# schematic.net
KiCad netlist of a schematic drawn in EAGLE
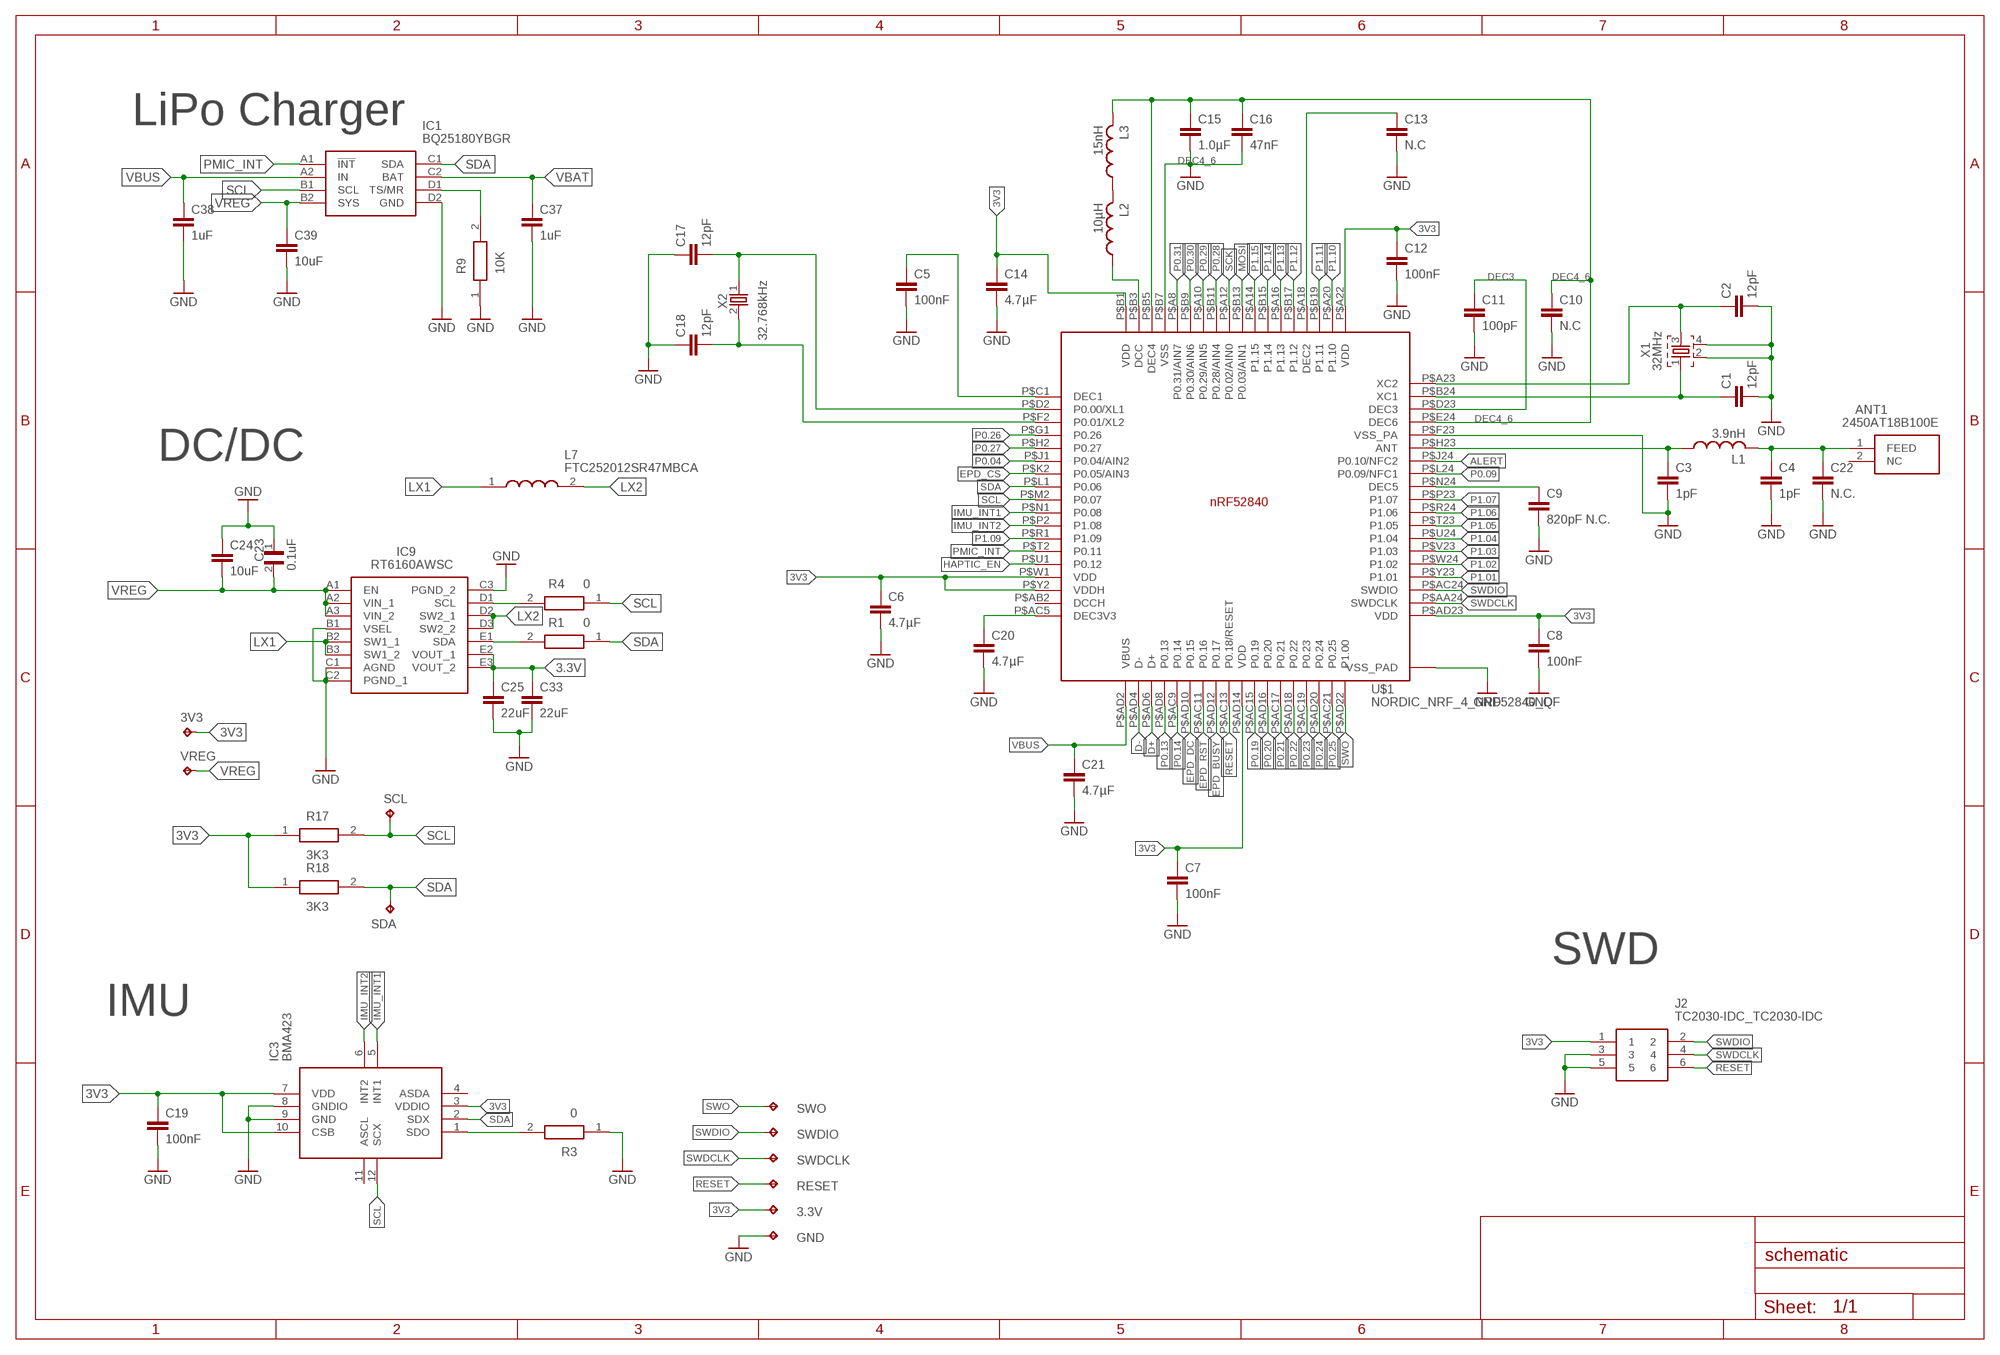
[diagram p0: schematic, sheet 1, part 1 of 2]
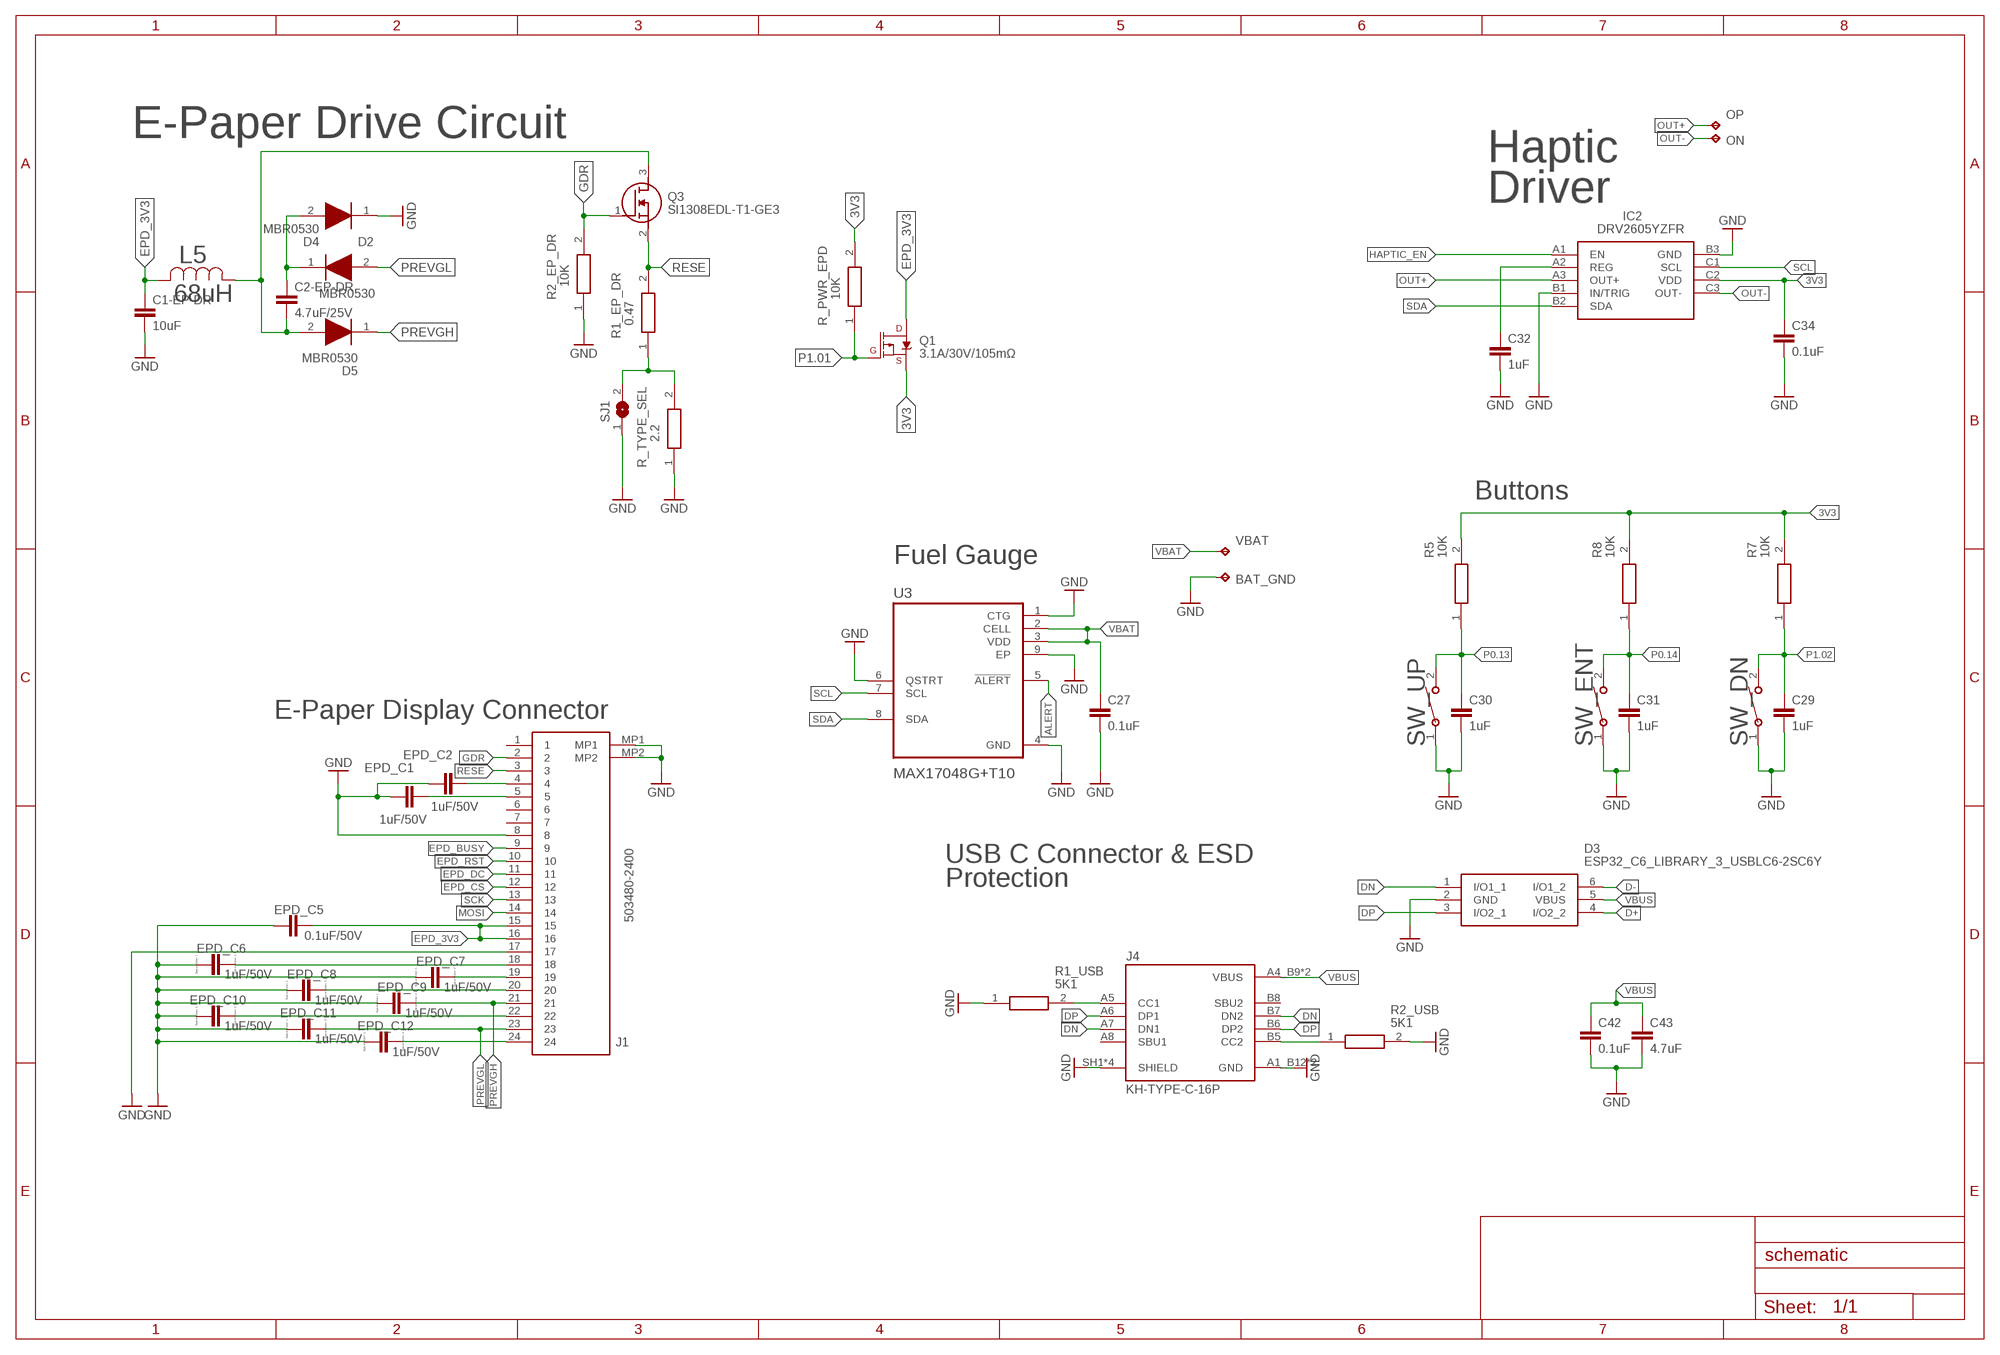
[diagram p1: schematic, sheet 1, part 2 of 2]

(export (version "E")
  (design (tool "Eeschema 10.0.6"))
  (components
    (comp (ref "3.3V")
      (value "HECTOR_WATCH_1_TPTP20R")
      (footprint "eagle-import:HECTOR_WATCH_1_TP20R")
      (libsource (lib "eagle-import") (part "HECTOR_WATCH_1_TPTP20R"))
    )
    (comp (ref "3V3")
      (value "HECTOR_WATCH_1_TPTP20R")
      (footprint "eagle-import:HECTOR_WATCH_1_TP20R")
      (libsource (lib "eagle-import") (part "HECTOR_WATCH_1_TPTP20R"))
    )
    (comp (ref "ANT1")
      (value "2450AT18B100E")
      (footprint "eagle-import:2450AT18B100E_ANTC3216X140N")
      (fields (field (name "MOUSER_PART_NUMBER") "609-2450AT18B100E"))
      (libsource (lib "eagle-import") (part "2450AT18B100E_2450AT18B100E"))
    )
    (comp (ref "BAT_GND")
      (value "HECTOR_WATCH_1_TPTP20R")
      (footprint "eagle-import:HECTOR_WATCH_1_TP20R")
      (libsource (lib "eagle-import") (part "HECTOR_WATCH_1_TPTP20R"))
    )
    (comp (ref "C1")
      (value "12pF")
      (footprint "eagle-import:NORDIC_NRF_3_RESC0201_N")
      (libsource (lib "eagle-import") (part "NORDIC_NRF_3_CAPACITOR_0201_N"))
    )
    (comp (ref "C1-EP-DR")
      (value "10uF")
      (footprint "eagle-import:NORDIC_NRF_3_RESC0402_N")
      (libsource (lib "eagle-import") (part "NORDIC_NRF_3_CAPACITOR_0402_N"))
    )
    (comp (ref "C2")
      (value "12pF")
      (footprint "eagle-import:NORDIC_NRF_3_RESC0201_N")
      (libsource (lib "eagle-import") (part "NORDIC_NRF_3_CAPACITOR_0201_N"))
    )
    (comp (ref "C2-EP-DR")
      (value "4.7uF/25V")
      (footprint "eagle-import:NORDIC_NRF_3_RESC0402_N")
      (libsource (lib "eagle-import") (part "NORDIC_NRF_3_CAPACITOR_0402_N"))
    )
    (comp (ref "C3")
      (value "1pF")
      (footprint "eagle-import:NORDIC_NRF_3_RESC0201_N")
      (libsource (lib "eagle-import") (part "NORDIC_NRF_3_CAPACITOR_0201_N"))
    )
    (comp (ref "C4")
      (value "1pF")
      (footprint "eagle-import:NORDIC_NRF_3_RESC0201_N")
      (libsource (lib "eagle-import") (part "NORDIC_NRF_3_CAPACITOR_0201_N"))
    )
    (comp (ref "C5")
      (value "100nF")
      (footprint "eagle-import:NORDIC_NRF_3_RESC0201_N")
      (libsource (lib "eagle-import") (part "NORDIC_NRF_3_CAPACITOR_0201_N"))
    )
    (comp (ref "C6")
      (value "4.7µF")
      (footprint "eagle-import:NORDIC_NRF_3_RESC0402_N")
      (libsource (lib "eagle-import") (part "NORDIC_NRF_3_CAPACITOR_0402_N"))
    )
    (comp (ref "C7")
      (value "100nF")
      (footprint "eagle-import:NORDIC_NRF_3_RESC0201_N")
      (libsource (lib "eagle-import") (part "NORDIC_NRF_3_CAPACITOR_0201_N"))
    )
    (comp (ref "C8")
      (value "100nF")
      (footprint "eagle-import:NORDIC_NRF_3_RESC0201_N")
      (libsource (lib "eagle-import") (part "NORDIC_NRF_3_CAPACITOR_0201_N"))
    )
    (comp (ref "C9")
      (value "820pF N.C.")
      (footprint "eagle-import:NORDIC_NRF_3_RESC0201_N")
      (libsource (lib "eagle-import") (part "NORDIC_NRF_3_CAPACITOR_0201_N"))
    )
    (comp (ref "C10")
      (value "N.C")
      (footprint "eagle-import:NORDIC_NRF_3_RESC0201_N")
      (libsource (lib "eagle-import") (part "NORDIC_NRF_3_CAPACITOR_0201_N"))
    )
    (comp (ref "C11")
      (value "100pF")
      (footprint "eagle-import:NORDIC_NRF_3_RESC0201_N")
      (libsource (lib "eagle-import") (part "NORDIC_NRF_3_CAPACITOR_0201_N"))
    )
    (comp (ref "C12")
      (value "100nF")
      (footprint "eagle-import:NORDIC_NRF_3_RESC0201_N")
      (libsource (lib "eagle-import") (part "NORDIC_NRF_3_CAPACITOR_0201_N"))
    )
    (comp (ref "C13")
      (value "N.C")
      (footprint "eagle-import:NORDIC_NRF_3_RESC0201_N")
      (libsource (lib "eagle-import") (part "NORDIC_NRF_3_CAPACITOR_0201_N"))
    )
    (comp (ref "C14")
      (value "4.7µF")
      (footprint "eagle-import:NORDIC_NRF_3_RESC0402_M")
      (libsource (lib "eagle-import") (part "NORDIC_NRF_3_CAPACITOR_0402_M"))
    )
    (comp (ref "C15")
      (value "1.0µF")
      (footprint "eagle-import:NORDIC_NRF_3_RESC0402_M")
      (libsource (lib "eagle-import") (part "NORDIC_NRF_3_CAPACITOR_0402_M"))
    )
    (comp (ref "C16")
      (value "47nF")
      (footprint "eagle-import:NORDIC_NRF_3_RESC0201_N")
      (libsource (lib "eagle-import") (part "NORDIC_NRF_3_CAPACITOR_0201_N"))
    )
    (comp (ref "C17")
      (value "12pF")
      (footprint "eagle-import:NORDIC_NRF_3_RESC0201_N")
      (libsource (lib "eagle-import") (part "NORDIC_NRF_3_CAPACITOR_0201_N"))
    )
    (comp (ref "C18")
      (value "12pF")
      (footprint "eagle-import:NORDIC_NRF_3_RESC0201_N")
      (libsource (lib "eagle-import") (part "NORDIC_NRF_3_CAPACITOR_0201_N"))
    )
    (comp (ref "C19")
      (value "100nF")
      (footprint "eagle-import:NORDIC_NRF_3_RESC0201_N")
      (libsource (lib "eagle-import") (part "NORDIC_NRF_3_CAPACITOR_0201_N"))
    )
    (comp (ref "C20")
      (value "4.7µF")
      (footprint "eagle-import:NORDIC_NRF_3_RESC0402_N")
      (libsource (lib "eagle-import") (part "NORDIC_NRF_3_CAPACITOR_0402_N"))
    )
    (comp (ref "C21")
      (value "4.7µF")
      (footprint "eagle-import:NORDIC_NRF_3_RESC0402_N")
      (libsource (lib "eagle-import") (part "NORDIC_NRF_3_CAPACITOR_0402_N"))
    )
    (comp (ref "C22")
      (value "N.C.")
      (footprint "eagle-import:NORDIC_NRF_3_RESC0201_N")
      (libsource (lib "eagle-import") (part "NORDIC_NRF_3_CAPACITOR_0201_N"))
    )
    (comp (ref "C23")
      (value "0.1uF")
      (footprint "eagle-import:GRM011R60J152KE01L_1_0201")
      (fields (field (name "MF") "Murata") (field (name "MP") "GRM011R60J152KE01L"))
      (libsource (lib "eagle-import") (part "GRM011R60J152KE01L_2_GRM011R60J152KE01L"))
    )
    (comp (ref "C24")
      (value "10uF")
      (footprint "eagle-import:NORDIC_NRF_3_RESC0402_N")
      (libsource (lib "eagle-import") (part "NORDIC_NRF_3_CAPACITOR_0402_N"))
    )
    (comp (ref "C25")
      (value "22uF")
      (footprint "eagle-import:NORDIC_NRF_3_RESC0402_N")
      (libsource (lib "eagle-import") (part "NORDIC_NRF_3_CAPACITOR_0402_N"))
    )
    (comp (ref "C27")
      (value "0.1uF")
      (footprint "eagle-import:NORDIC_NRF_3_RESC0201_N")
      (libsource (lib "eagle-import") (part "NORDIC_NRF_3_CAPACITOR_0201_N"))
    )
    (comp (ref "C29")
      (value "1uF")
      (footprint "eagle-import:NORDIC_NRF_3_RESC0402_N")
      (libsource (lib "eagle-import") (part "NORDIC_NRF_3_CAPACITOR_0402_N"))
    )
    (comp (ref "C30")
      (value "1uF")
      (footprint "eagle-import:NORDIC_NRF_3_RESC0402_N")
      (libsource (lib "eagle-import") (part "NORDIC_NRF_3_CAPACITOR_0402_N"))
    )
    (comp (ref "C31")
      (value "1uF")
      (footprint "eagle-import:NORDIC_NRF_3_RESC0402_N")
      (libsource (lib "eagle-import") (part "NORDIC_NRF_3_CAPACITOR_0402_N"))
    )
    (comp (ref "C32")
      (value "1uF")
      (footprint "eagle-import:NORDIC_NRF_3_RESC0402_N")
      (libsource (lib "eagle-import") (part "NORDIC_NRF_3_CAPACITOR_0402_N"))
    )
    (comp (ref "C33")
      (value "22uF")
      (footprint "eagle-import:NORDIC_NRF_3_RESC0402_N")
      (libsource (lib "eagle-import") (part "NORDIC_NRF_3_CAPACITOR_0402_N"))
    )
    (comp (ref "C34")
      (value "0.1uF")
      (footprint "eagle-import:NORDIC_NRF_3_RESC0201_N")
      (libsource (lib "eagle-import") (part "NORDIC_NRF_3_CAPACITOR_0201_N"))
    )
    (comp (ref "C37")
      (value "1uF")
      (footprint "eagle-import:NORDIC_NRF_3_RESC0402_N")
      (libsource (lib "eagle-import") (part "NORDIC_NRF_3_CAPACITOR_0402_N"))
    )
    (comp (ref "C38")
      (value "1uF")
      (footprint "eagle-import:NORDIC_NRF_3_RESC0402_N")
      (libsource (lib "eagle-import") (part "NORDIC_NRF_3_CAPACITOR_0402_N"))
    )
    (comp (ref "C39")
      (value "10uF")
      (footprint "eagle-import:NORDIC_NRF_3_RESC0402_N")
      (libsource (lib "eagle-import") (part "NORDIC_NRF_3_CAPACITOR_0402_N"))
    )
    (comp (ref "C42")
      (value "0.1uF")
      (footprint "eagle-import:NORDIC_NRF_3_RESC0201_N")
      (libsource (lib "eagle-import") (part "NORDIC_NRF_3_CAPACITOR_0201_N"))
    )
    (comp (ref "C43")
      (value "4.7uF")
      (footprint "eagle-import:NORDIC_NRF_3_RESC0402_N")
      (libsource (lib "eagle-import") (part "NORDIC_NRF_3_CAPACITOR_0402_N"))
    )
    (comp (ref "D2")
      (value "MBR0530")
      (footprint "eagle-import:ESP32_C6_LIBRARY_5_SOD3716X135N")
      (fields (field (name "MF") "ON Semiconductor"))
      (libsource (lib "eagle-import") (part "ESP32_C6_LIBRARY_5_MBR0530"))
    )
    (comp (ref "D3")
      (value "ESP32_C6_LIBRARY_3_USBLC6-2SC6Y")
      (footprint "eagle-import:ESP32_C6_LIBRARY_3_SOT95P280X145-6N")
      (fields (field (name "MF") "STMicroelectronics") (field (name "MP") "USBLC6-2SC6Y"))
      (libsource (lib "eagle-import") (part "ESP32_C6_LIBRARY_3_USBLC6-2SC6Y"))
    )
    (comp (ref "D4")
      (value "MBR0530")
      (footprint "eagle-import:ESP32_C6_LIBRARY_5_SOD3716X135N")
      (fields (field (name "MF") "ON Semiconductor"))
      (libsource (lib "eagle-import") (part "ESP32_C6_LIBRARY_5_MBR0530"))
    )
    (comp (ref "D5")
      (value "MBR0530")
      (footprint "eagle-import:ESP32_C6_LIBRARY_5_SOD3716X135N")
      (fields (field (name "MF") "ON Semiconductor"))
      (libsource (lib "eagle-import") (part "ESP32_C6_LIBRARY_5_MBR0530"))
    )
    (comp (ref "EPD_C1")
      (value "1uF/50V")
      (footprint "eagle-import:NORDIC_NRF_3_RESC0402_N")
      (libsource (lib "eagle-import") (part "NORDIC_NRF_3_CAPACITOR_0402_N"))
    )
    (comp (ref "EPD_C2")
      (value "1uF/50V")
      (footprint "eagle-import:NORDIC_NRF_3_RESC0402_N")
      (libsource (lib "eagle-import") (part "NORDIC_NRF_3_CAPACITOR_0402_N"))
    )
    (comp (ref "EPD_C5")
      (value "0.1uF/50V")
      (footprint "eagle-import:NORDIC_NRF_3_RESC0201_N")
      (libsource (lib "eagle-import") (part "NORDIC_NRF_3_CAPACITOR_0201_N"))
    )
    (comp (ref "EPD_C6")
      (value "1uF/50V")
      (footprint "eagle-import:ESP32_C6_LIBRARY_1_ESP32_WROVER_EAGLE-LTSPICE_C0402")
      (libsource (lib "eagle-import") (part "ESP32_C6_LIBRARY_1_ESP32_WROVER_EAGLE-LTSPICE_CC0402"))
    )
    (comp (ref "EPD_C7")
      (value "1uF/50V")
      (footprint "eagle-import:ESP32_C6_LIBRARY_1_ESP32_WROVER_EAGLE-LTSPICE_C0402")
      (libsource (lib "eagle-import") (part "ESP32_C6_LIBRARY_1_ESP32_WROVER_EAGLE-LTSPICE_CC0402"))
    )
    (comp (ref "EPD_C8")
      (value "1uF/50V")
      (footprint "eagle-import:ESP32_C6_LIBRARY_1_ESP32_WROVER_EAGLE-LTSPICE_C0402")
      (libsource (lib "eagle-import") (part "ESP32_C6_LIBRARY_1_ESP32_WROVER_EAGLE-LTSPICE_CC0402"))
    )
    (comp (ref "EPD_C9")
      (value "1uF/50V")
      (footprint "eagle-import:ESP32_C6_LIBRARY_1_ESP32_WROVER_EAGLE-LTSPICE_C0402")
      (libsource (lib "eagle-import") (part "ESP32_C6_LIBRARY_1_ESP32_WROVER_EAGLE-LTSPICE_CC0402"))
    )
    (comp (ref "EPD_C10")
      (value "1uF/50V")
      (footprint "eagle-import:ESP32_C6_LIBRARY_1_ESP32_WROVER_EAGLE-LTSPICE_C0402")
      (libsource (lib "eagle-import") (part "ESP32_C6_LIBRARY_1_ESP32_WROVER_EAGLE-LTSPICE_CC0402"))
    )
    (comp (ref "EPD_C11")
      (value "1uF/50V")
      (footprint "eagle-import:ESP32_C6_LIBRARY_1_ESP32_WROVER_EAGLE-LTSPICE_C0402")
      (libsource (lib "eagle-import") (part "ESP32_C6_LIBRARY_1_ESP32_WROVER_EAGLE-LTSPICE_CC0402"))
    )
    (comp (ref "EPD_C12")
      (value "1uF/50V")
      (footprint "eagle-import:ESP32_C6_LIBRARY_1_ESP32_WROVER_EAGLE-LTSPICE_C0402")
      (libsource (lib "eagle-import") (part "ESP32_C6_LIBRARY_1_ESP32_WROVER_EAGLE-LTSPICE_CC0402"))
    )
    (comp (ref "GND")
      (value "HECTOR_WATCH_1_TPTP20R")
      (footprint "eagle-import:HECTOR_WATCH_1_TP20R")
      (libsource (lib "eagle-import") (part "HECTOR_WATCH_1_TPTP20R"))
    )
    (comp (ref "IC1")
      (value "BQ25180YBGR")
      (footprint "eagle-import:BQ25180YBGR_BGA8C40P2X4_100X155X50")
      (fields (field (name "MOUSER_PART_NUMBER") "595-BQ25180YBGR"))
      (libsource (lib "eagle-import") (part "BQ25180YBGR_BQ25180YBGR"))
    )
    (comp (ref "IC2")
      (value "DRV2605YZFR")
      (footprint "eagle-import:DRV2605YZFR_BGA9C50P3X3_144X144X62")
      (libsource (lib "eagle-import") (part "DRV2605YZFR_DRV2605YZFR"))
    )
    (comp (ref "IC3")
      (value "BMA423")
      (footprint "eagle-import:BMA423_BMA423")
      (fields (field (name "MOUSER_PART_NUMBER") "262-BMA423"))
      (libsource (lib "eagle-import") (part "BMA423_BMA423"))
    )
    (comp (ref "IC9")
      (value "RT6160AWSC")
      (footprint "eagle-import:RT6160AWSC_BGA15C40P3X5_140X230X60")
      (fields (field (name "MOUSER_PART_NUMBER") "835-RT6160AWSC"))
      (libsource (lib "eagle-import") (part "RT6160AWSC_RT6160AWSC"))
    )
    (comp (ref "J1")
      (value "503480-2400")
      (footprint "eagle-import:503480-2400_5034802400")
      (fields (field (name "MOUSER_PART_NUMBER") "538-503480-2400"))
      (libsource (lib "eagle-import") (part "503480-2400_503480-2400"))
    )
    (comp (ref "J2")
      (value "TC2030-IDC_TC2030-IDC")
      (footprint "eagle-import:TC2030-IDC_TC2030IDC")
      (fields (field (name "MANUFACTURER_PART_NUMBER") "TC2030-IDC"))
      (libsource (lib "eagle-import") (part "TC2030-IDC_TC2030-IDC"))
    )
    (comp (ref "J4")
      (value "KH-TYPE-C-16P")
      (footprint "eagle-import:KH-TYPE-C-16P_KINGHELM_KH-TYPE-C-16P")
      (fields (field (name "MF") "kinghelm"))
      (libsource (lib "eagle-import") (part "KH-TYPE-C-16P_KH-TYPE-C-16P"))
    )
    (comp (ref "L1")
      (value "3.9nH")
      (footprint "eagle-import:NORDIC_NRF_2_RESC0402_N")
      (libsource (lib "eagle-import") (part "NORDIC_NRF_2_INDUCTOR_0402_N"))
    )
    (comp (ref "L2")
      (value "10µH")
      (footprint "eagle-import:NORDIC_NRF_2_RESC0603_N")
      (libsource (lib "eagle-import") (part "NORDIC_NRF_2_INDUCTOR_0603_N"))
    )
    (comp (ref "L3")
      (value "15nH")
      (footprint "eagle-import:NORDIC_NRF_2_RESC0402_N")
      (libsource (lib "eagle-import") (part "NORDIC_NRF_2_INDUCTOR_0402_N"))
    )
    (comp (ref "L5")
      (value "68uH")
      (footprint "eagle-import:ESP32_C6_LIBRARY_2_IND_4828-WE-TPC_WRE")
      (fields
        (field (name "MANUFACTURER_PART_NUMBER") "744043680")
        (field (name "COPYRIGHT") "Copyright (C) 2024 Ultra Librarian. All rights reserved.")
      )
      (libsource (lib "eagle-import") (part "ESP32_C6_LIBRARY_2_744043680IND_4828-WE-TPC_WRE"))
    )
    (comp (ref "L7")
      (value "FTC252012SR47MBCA")
      (footprint "eagle-import:MLP2016SR47MT0S1_INDC2016X100N")
      (libsource (lib "eagle-import") (part "MLP2016SR47MT0S1_FTC252012SR47MBCA"))
    )
    (comp (ref "ON")
      (value "HECTOR_WATCH_1_TPTP20R")
      (footprint "eagle-import:HECTOR_WATCH_1_TP20R")
      (libsource (lib "eagle-import") (part "HECTOR_WATCH_1_TPTP20R"))
    )
    (comp (ref "OP")
      (value "HECTOR_WATCH_1_TPTP20R")
      (footprint "eagle-import:HECTOR_WATCH_1_TP20R")
      (libsource (lib "eagle-import") (part "HECTOR_WATCH_1_TPTP20R"))
    )
    (comp (ref "Q1")
      (value "3.1A/30V/105mΩ")
      (footprint "eagle-import:ESP32_C6_LIBRARY_4_ESP32_C6_LIBRARY_4_ESP32_C6_LIBRARY_4_ESP32_C6_LIBRARY_4_ESP32_WROVER_SPARKFUN-DISCRETESEMI_SOT23-3")
      (libsource (lib "eagle-import") (part "ESP32_C6_LIBRARY_4_ESP32_WROVER_SPARKFUN-DISCRETESEMI_MOSFET_PCH-DMG2307L"))
    )
    (comp (ref "Q3")
      (value "SI1308EDL-T1-GE3")
      (footprint "eagle-import:ESP32_C6_LIBRARY_6_SOT65P210X110-3N")
      (fields (field (name "MF") "Vishay Siliconix"))
      (libsource (lib "eagle-import") (part "ESP32_C6_LIBRARY_6_SI1308EDL-T1-GE3"))
    )
    (comp (ref "R1")
      (value "0")
      (footprint "eagle-import:ERA-1AEB3401C_0201")
      (libsource (lib "eagle-import") (part "ERA-1AEB3401C_CPF0201D7K68C1"))
    )
    (comp (ref "R1_EP_DR")
      (value "0.47")
      (footprint "eagle-import:CPF0201D7K68C1_0201")
      (libsource (lib "eagle-import") (part "CPF0201D7K68C1_CPF0201D7K68C1"))
    )
    (comp (ref "R1_USB")
      (value "5K1")
      (footprint "eagle-import:ERA-1AEB3401C_0201")
      (libsource (lib "eagle-import") (part "ERA-1AEB3401C_CPF0201D7K68C1"))
    )
    (comp (ref "R2_EP_DR")
      (value "10K")
      (footprint "eagle-import:CPF0201D7K68C1_0201")
      (libsource (lib "eagle-import") (part "CPF0201D7K68C1_CPF0201D7K68C1"))
    )
    (comp (ref "R2_USB")
      (value "5K1")
      (footprint "eagle-import:ERA-1AEB3401C_0201")
      (libsource (lib "eagle-import") (part "ERA-1AEB3401C_CPF0201D7K68C1"))
    )
    (comp (ref "R3")
      (value "0")
      (footprint "eagle-import:ERA-1AEB3401C_0201")
      (libsource (lib "eagle-import") (part "ERA-1AEB3401C_CPF0201D7K68C1"))
    )
    (comp (ref "R4")
      (value "0")
      (footprint "eagle-import:ERA-1AEB3401C_0201")
      (libsource (lib "eagle-import") (part "ERA-1AEB3401C_CPF0201D7K68C1"))
    )
    (comp (ref "R5")
      (value "10K")
      (footprint "eagle-import:CPF0201D7K68C1_0201")
      (libsource (lib "eagle-import") (part "CPF0201D7K68C1_CPF0201D7K68C1"))
    )
    (comp (ref "R7")
      (value "10K")
      (footprint "eagle-import:ERA-1AEB3401C_0201")
      (libsource (lib "eagle-import") (part "ERA-1AEB3401C_CPF0201D7K68C1"))
    )
    (comp (ref "R8")
      (value "10K")
      (footprint "eagle-import:CPF0201D7K68C1_0201")
      (libsource (lib "eagle-import") (part "CPF0201D7K68C1_CPF0201D7K68C1"))
    )
    (comp (ref "R9")
      (value "10K")
      (footprint "eagle-import:CPF0201D7K68C1_0201")
      (libsource (lib "eagle-import") (part "CPF0201D7K68C1_CPF0201D7K68C1"))
    )
    (comp (ref "R17")
      (value "3K3")
      (footprint "eagle-import:CPF0201D7K68C1_0201")
      (libsource (lib "eagle-import") (part "CPF0201D7K68C1_CPF0201D7K68C1"))
    )
    (comp (ref "R18")
      (value "3K3")
      (footprint "eagle-import:CPF0201D7K68C1_0201")
      (libsource (lib "eagle-import") (part "CPF0201D7K68C1_CPF0201D7K68C1"))
    )
    (comp (ref "RESET")
      (value "HECTOR_WATCH_1_TPTP20R")
      (footprint "eagle-import:HECTOR_WATCH_1_TP20R")
      (libsource (lib "eagle-import") (part "HECTOR_WATCH_1_TPTP20R"))
    )
    (comp (ref "R_PWR_EPD")
      (value "10K")
      (footprint "eagle-import:ERA-1AEB3401C_0201")
      (libsource (lib "eagle-import") (part "ERA-1AEB3401C_CPF0201D7K68C1"))
    )
    (comp (ref "R_TYPE_SEL")
      (value "2.2")
      (footprint "eagle-import:ERA-1AEB3401C_0201")
      (libsource (lib "eagle-import") (part "ERA-1AEB3401C_CPF0201D7K68C1"))
    )
    (comp (ref "SCL")
      (value "HECTOR_WATCH_1_TPTP20R")
      (footprint "eagle-import:HECTOR_WATCH_1_TP20R")
      (libsource (lib "eagle-import") (part "HECTOR_WATCH_1_TPTP20R"))
    )
    (comp (ref "SDA")
      (value "HECTOR_WATCH_1_TPTP20R")
      (footprint "eagle-import:HECTOR_WATCH_1_TP20R")
      (libsource (lib "eagle-import") (part "HECTOR_WATCH_1_TPTP20R"))
    )
    (comp (ref "SJ1")
      (value "ESP32_C6_LIBRARY_7_JUMPER_SJ")
      (footprint "eagle-import:ESP32_C6_LIBRARY_7_JUMPER_SJ")
      (libsource (lib "eagle-import") (part "ESP32_C6_LIBRARY_7_JUMPER_SJ"))
    )
    (comp (ref "SWDCLK")
      (value "HECTOR_WATCH_1_TPTP20R")
      (footprint "eagle-import:HECTOR_WATCH_1_TP20R")
      (libsource (lib "eagle-import") (part "HECTOR_WATCH_1_TPTP20R"))
    )
    (comp (ref "SWDIO")
      (value "HECTOR_WATCH_1_TPTP20R")
      (footprint "eagle-import:HECTOR_WATCH_1_TP20R")
      (libsource (lib "eagle-import") (part "HECTOR_WATCH_1_TPTP20R"))
    )
    (comp (ref "SWO")
      (value "HECTOR_WATCH_1_TPTP20R")
      (footprint "eagle-import:HECTOR_WATCH_1_TP20R")
      (libsource (lib "eagle-import") (part "HECTOR_WATCH_1_TPTP20R"))
    )
    (comp (ref "SW_DN")
      (value "2025-10-22_07-23-44_LIBRARY_EVP-AKE31ASW_EVP-AKE31A_PAN")
      (footprint "eagle-import:2025-10-22_07-23-44_LIBRARY_SW_EVP-AKE31A_PAN")
      (fields
        (field (name "MANUFACTURER_PART_NUMBER") "EVP-AKE31A")
        (field (name "COPYRIGHT") "Copyright (C) 2025 Ultra Librarian. All rights reserved.")
      )
      (libsource (lib "eagle-import") (part "2025-10-22_07-23-44_LIBRARY_EVP-AKE31ASW_EVP-AKE31A_PAN"))
    )
    (comp (ref "SW_ENT")
      (value "2025-10-22_07-23-44_LIBRARY_EVP-AKE31ASW_EVP-AKE31A_PAN")
      (footprint "eagle-import:2025-10-22_07-23-44_LIBRARY_SW_EVP-AKE31A_PAN")
      (fields
        (field (name "MANUFACTURER_PART_NUMBER") "EVP-AKE31A")
        (field (name "COPYRIGHT") "Copyright (C) 2025 Ultra Librarian. All rights reserved.")
      )
      (libsource (lib "eagle-import") (part "2025-10-22_07-23-44_LIBRARY_EVP-AKE31ASW_EVP-AKE31A_PAN"))
    )
    (comp (ref "SW_UP")
      (value "2025-10-22_07-23-44_LIBRARY_EVP-AKE31ASW_EVP-AKE31A_PAN")
      (footprint "eagle-import:2025-10-22_07-23-44_LIBRARY_SW_EVP-AKE31A_PAN")
      (fields
        (field (name "MANUFACTURER_PART_NUMBER") "EVP-AKE31A")
        (field (name "COPYRIGHT") "Copyright (C) 2025 Ultra Librarian. All rights reserved.")
      )
      (libsource (lib "eagle-import") (part "2025-10-22_07-23-44_LIBRARY_EVP-AKE31ASW_EVP-AKE31A_PAN"))
    )
    (comp (ref "U$1")
      (value "NORDIC_NRF_4_NRF52840_QF")
      (footprint "eagle-import:NORDIC_NRF_4_AQFN50P700X700X85_HS-74N")
      (libsource (lib "eagle-import") (part "NORDIC_NRF_4_NRF52840_QF"))
    )
    (comp (ref "U3")
      (value "MAX17048G+T10")
      (footprint "eagle-import:ESP32_C6_LIBRARY_SON50P200X200X80-9N")
      (fields (field (name "MF") "Analog Devices"))
      (libsource (lib "eagle-import") (part "ESP32_C6_LIBRARY_MAX17048G+T10"))
    )
    (comp (ref "VBAT")
      (value "HECTOR_WATCH_1_TPTP20R")
      (footprint "eagle-import:HECTOR_WATCH_1_TP20R")
      (libsource (lib "eagle-import") (part "HECTOR_WATCH_1_TPTP20R"))
    )
    (comp (ref "VREG")
      (value "HECTOR_WATCH_1_TPTP20R")
      (footprint "eagle-import:HECTOR_WATCH_1_TP20R")
      (libsource (lib "eagle-import") (part "HECTOR_WATCH_1_TPTP20R"))
    )
    (comp (ref "X1")
      (value "32MHz")
      (footprint "eagle-import:NORDIC_NRF_BT-XTAL_2016_N")
      (libsource (lib "eagle-import") (part "NORDIC_NRF_XTAL_32MHZ"))
    )
    (comp (ref "X2")
      (value "32.768kHz")
      (footprint "eagle-import:NORDIC_NRF_1_XTAL_3215_N")
      (libsource (lib "eagle-import") (part "NORDIC_NRF_1_XTAL_32KHZ"))
    )
  )
  (nets
    (net (code "1") (name "/DEC3") (class "Default")
      (node (ref "C11") (pin "1") (pinfunction "1_1") (pintype "passive"))
      (node (ref "U$1") (pin "P$D23") (pinfunction "DEC3_P$D23") (pintype "bidirectional"))
    )
    (net (code "2") (name "/DEC4_6") (class "Default")
      (node (ref "C10") (pin "1") (pinfunction "1_1") (pintype "passive"))
      (node (ref "C15") (pin "1") (pinfunction "1_1") (pintype "passive"))
      (node (ref "C16") (pin "1") (pinfunction "1_1") (pintype "passive"))
      (node (ref "L3") (pin "2") (pinfunction "2_2") (pintype "passive"))
      (node (ref "U$1") (pin "P$B5") (pinfunction "DEC4_P$B5") (pintype "power_in"))
      (node (ref "U$1") (pin "P$E24") (pinfunction "DEC6_P$E24") (pintype "bidirectional"))
    )
    (net (code "3") (name "3.3V") (class "Default")
      (node (ref "C25") (pin "1") (pinfunction "1_1") (pintype "passive"))
      (node (ref "C33") (pin "1") (pinfunction "1_1") (pintype "passive"))
      (node (ref "IC9") (pin "E2") (pinfunction "VOUT_1_E2") (pintype "bidirectional"))
      (node (ref "IC9") (pin "E3") (pinfunction "VOUT_2_E3") (pintype "bidirectional"))
    )
    (net (code "4") (name "3V3") (class "Default")
      (node (ref "3.3V") (pin "TP") (pinfunction "TP_TP") (pintype "input"))
      (node (ref "3V3") (pin "TP") (pinfunction "TP_TP") (pintype "input"))
      (node (ref "C12") (pin "1") (pinfunction "1_1") (pintype "passive"))
      (node (ref "C14") (pin "1") (pinfunction "1_1") (pintype "passive"))
      (node (ref "C19") (pin "1") (pinfunction "1_1") (pintype "passive"))
      (node (ref "C34") (pin "1") (pinfunction "1_1") (pintype "passive"))
      (node (ref "C6") (pin "1") (pinfunction "1_1") (pintype "passive"))
      (node (ref "C7") (pin "1") (pinfunction "1_1") (pintype "passive"))
      (node (ref "C8") (pin "1") (pinfunction "1_1") (pintype "passive"))
      (node (ref "IC2") (pin "C2") (pinfunction "VDD_C2") (pintype "bidirectional"))
      (node (ref "IC3") (pin "10") (pinfunction "CSB_10") (pintype "bidirectional"))
      (node (ref "IC3") (pin "3") (pinfunction "VDDIO_3") (pintype "bidirectional"))
      (node (ref "IC3") (pin "7") (pinfunction "VDD_7") (pintype "bidirectional"))
      (node (ref "J2") (pin "1") (pinfunction "1_1") (pintype "bidirectional"))
      (node (ref "Q1") (pin "2") (pinfunction "S_2") (pintype "bidirectional"))
      (node (ref "R17") (pin "1") (pinfunction "1_1") (pintype "bidirectional"))
      (node (ref "R18") (pin "1") (pinfunction "1_1") (pintype "bidirectional"))
      (node (ref "R5") (pin "2") (pinfunction "2_2") (pintype "bidirectional"))
      (node (ref "R7") (pin "2") (pinfunction "2_2") (pintype "bidirectional"))
      (node (ref "R8") (pin "2") (pinfunction "2_2") (pintype "bidirectional"))
      (node (ref "R_PWR_EPD") (pin "2") (pinfunction "2_2") (pintype "bidirectional"))
      (node (ref "U$1") (pin "P$A22") (pinfunction "VDD_P$A22") (pintype "power_in"))
      (node (ref "U$1") (pin "P$AD14") (pinfunction "VDD_P$AD14") (pintype "power_in"))
      (node (ref "U$1") (pin "P$AD23") (pinfunction "VDD_P$AD23") (pintype "power_in"))
      (node (ref "U$1") (pin "P$B1") (pinfunction "VDD_P$B1") (pintype "power_in"))
      (node (ref "U$1") (pin "P$W1") (pinfunction "VDD_P$W1") (pintype "power_in"))
      (node (ref "U$1") (pin "P$Y2") (pinfunction "VDDH_P$Y2") (pintype "power_in"))
    )
    (net (code "5") (name "ALERT") (class "Default")
      (node (ref "U$1") (pin "P$J24") (pinfunction "P0.10/NFC2_P$J24") (pintype "bidirectional"))
      (node (ref "U3") (pin "5") (pinfunction "~{ALERT}_5") (pintype "output"))
    )
    (net (code "6") (name "D+") (class "Default")
      (node (ref "D3") (pin "4") (pinfunction "I/O2_2_4") (pintype "bidirectional"))
      (node (ref "U$1") (pin "P$AD6") (pinfunction "D+_P$AD6") (pintype "bidirectional"))
    )
    (net (code "7") (name "D-") (class "Default")
      (node (ref "D3") (pin "6") (pinfunction "I/O1_2_6") (pintype "bidirectional"))
      (node (ref "U$1") (pin "P$AD4") (pinfunction "D-_P$AD4") (pintype "bidirectional"))
    )
    (net (code "8") (name "DN") (class "Default")
      (node (ref "D3") (pin "1") (pinfunction "I/O1_1_1") (pintype "bidirectional"))
      (node (ref "J4") (pin "A7") (pinfunction "DN1_A7") (pintype "bidirectional"))
      (node (ref "J4") (pin "B7") (pinfunction "DN2_B7") (pintype "bidirectional"))
    )
    (net (code "9") (name "DP") (class "Default")
      (node (ref "D3") (pin "3") (pinfunction "I/O2_1_3") (pintype "bidirectional"))
      (node (ref "J4") (pin "A6") (pinfunction "DP1_A6") (pintype "bidirectional"))
      (node (ref "J4") (pin "B6") (pinfunction "DP2_B6") (pintype "bidirectional"))
    )
    (net (code "10") (name "EPD_3V3") (class "Default")
      (node (ref "C1-EP-DR") (pin "1") (pinfunction "1_1") (pintype "passive"))
      (node (ref "EPD_C5") (pin "2") (pinfunction "2_2") (pintype "passive"))
      (node (ref "J1") (pin "15") (pinfunction "15_15") (pintype "bidirectional"))
      (node (ref "J1") (pin "16") (pinfunction "16_16") (pintype "bidirectional"))
      (node (ref "L5") (pin "2") (pinfunction "2_2") (pintype "passive"))
      (node (ref "Q1") (pin "3") (pinfunction "D_3") (pintype "bidirectional"))
    )
    (net (code "11") (name "EPD_BUSY") (class "Default")
      (node (ref "J1") (pin "9") (pinfunction "9_9") (pintype "bidirectional"))
      (node (ref "U$1") (pin "P$AD12") (pinfunction "P0.17_P$AD12") (pintype "bidirectional"))
    )
    (net (code "12") (name "EPD_CS") (class "Default")
      (node (ref "J1") (pin "12") (pinfunction "12_12") (pintype "bidirectional"))
      (node (ref "U$1") (pin "P$K2") (pinfunction "P0.05/AIN3_P$K2") (pintype "bidirectional"))
    )
    (net (code "13") (name "EPD_DC") (class "Default")
      (node (ref "J1") (pin "11") (pinfunction "11_11") (pintype "bidirectional"))
      (node (ref "U$1") (pin "P$AD10") (pinfunction "P0.15_P$AD10") (pintype "bidirectional"))
    )
    (net (code "14") (name "EPD_RST") (class "Default")
      (node (ref "J1") (pin "10") (pinfunction "10_10") (pintype "bidirectional"))
      (node (ref "U$1") (pin "P$AC11") (pinfunction "P0.16_P$AC11") (pintype "bidirectional"))
    )
    (net (code "15") (name "GDR") (class "Default")
      (node (ref "J1") (pin "2") (pinfunction "2_2") (pintype "bidirectional"))
      (node (ref "Q3") (pin "1") (pinfunction "G_1") (pintype "bidirectional"))
      (node (ref "R2_EP_DR") (pin "2") (pinfunction "2_2") (pintype "bidirectional"))
    )
    (net (code "16") (name "GND") (class "Default")
      (node (ref "BAT_GND") (pin "TP") (pinfunction "TP_TP") (pintype "input"))
      (node (ref "C1") (pin "2") (pinfunction "2_2") (pintype "passive"))
      (node (ref "C1-EP-DR") (pin "2") (pinfunction "2_2") (pintype "passive"))
      (node (ref "C10") (pin "2") (pinfunction "2_2") (pintype "passive"))
      (node (ref "C11") (pin "2") (pinfunction "2_2") (pintype "passive"))
      (node (ref "C12") (pin "2") (pinfunction "2_2") (pintype "passive"))
      (node (ref "C13") (pin "2") (pinfunction "2_2") (pintype "passive"))
      (node (ref "C14") (pin "2") (pinfunction "2_2") (pintype "passive"))
      (node (ref "C15") (pin "2") (pinfunction "2_2") (pintype "passive"))
      (node (ref "C16") (pin "2") (pinfunction "2_2") (pintype "passive"))
      (node (ref "C17") (pin "1") (pinfunction "1_1") (pintype "passive"))
      (node (ref "C18") (pin "1") (pinfunction "1_1") (pintype "passive"))
      (node (ref "C19") (pin "2") (pinfunction "2_2") (pintype "passive"))
      (node (ref "C2") (pin "2") (pinfunction "2_2") (pintype "passive"))
      (node (ref "C20") (pin "2") (pinfunction "2_2") (pintype "passive"))
      (node (ref "C21") (pin "2") (pinfunction "2_2") (pintype "passive"))
      (node (ref "C22") (pin "2") (pinfunction "2_2") (pintype "passive"))
      (node (ref "C23") (pin "1") (pinfunction "1_1") (pintype "passive"))
      (node (ref "C24") (pin "1") (pinfunction "1_1") (pintype "passive"))
      (node (ref "C25") (pin "2") (pinfunction "2_2") (pintype "passive"))
      (node (ref "C27") (pin "2") (pinfunction "2_2") (pintype "passive"))
      (node (ref "C29") (pin "2") (pinfunction "2_2") (pintype "passive"))
      (node (ref "C3") (pin "2") (pinfunction "2_2") (pintype "passive"))
      (node (ref "C30") (pin "2") (pinfunction "2_2") (pintype "passive"))
      (node (ref "C31") (pin "2") (pinfunction "2_2") (pintype "passive"))
      (node (ref "C32") (pin "2") (pinfunction "2_2") (pintype "passive"))
      (node (ref "C33") (pin "2") (pinfunction "2_2") (pintype "passive"))
      (node (ref "C34") (pin "2") (pinfunction "2_2") (pintype "passive"))
      (node (ref "C37") (pin "2") (pinfunction "2_2") (pintype "passive"))
      (node (ref "C38") (pin "2") (pinfunction "2_2") (pintype "passive"))
      (node (ref "C39") (pin "2") (pinfunction "2_2") (pintype "passive"))
      (node (ref "C4") (pin "2") (pinfunction "2_2") (pintype "passive"))
      (node (ref "C42") (pin "2") (pinfunction "2_2") (pintype "passive"))
      (node (ref "C43") (pin "2") (pinfunction "2_2") (pintype "passive"))
      (node (ref "C5") (pin "2") (pinfunction "2_2") (pintype "passive"))
      (node (ref "C6") (pin "2") (pinfunction "2_2") (pintype "passive"))
      (node (ref "C7") (pin "2") (pinfunction "2_2") (pintype "passive"))
      (node (ref "C8") (pin "2") (pinfunction "2_2") (pintype "passive"))
      (node (ref "C9") (pin "2") (pinfunction "2_2") (pintype "passive"))
      (node (ref "D3") (pin "2") (pinfunction "GND_2") (pintype "bidirectional"))
      (node (ref "D4") (pin "1") (pinfunction "K_1") (pintype "bidirectional"))
      (node (ref "EPD_C1") (pin "1") (pinfunction "1_1") (pintype "passive"))
      (node (ref "EPD_C10") (pin "1") (pinfunction "1_1") (pintype "passive"))
      (node (ref "EPD_C11") (pin "1") (pinfunction "1_1") (pintype "passive"))
      (node (ref "EPD_C12") (pin "1") (pinfunction "1_1") (pintype "passive"))
      (node (ref "EPD_C2") (pin "1") (pinfunction "1_1") (pintype "passive"))
      (node (ref "EPD_C5") (pin "1") (pinfunction "1_1") (pintype "passive"))
      (node (ref "EPD_C6") (pin "1") (pinfunction "1_1") (pintype "passive"))
      (node (ref "EPD_C7") (pin "1") (pinfunction "1_1") (pintype "passive"))
      (node (ref "EPD_C8") (pin "1") (pinfunction "1_1") (pintype "passive"))
      (node (ref "EPD_C9") (pin "1") (pinfunction "1_1") (pintype "passive"))
      (node (ref "GND") (pin "TP") (pinfunction "TP_TP") (pintype "input"))
      (node (ref "IC1") (pin "D2") (pinfunction "GND_D2") (pintype "bidirectional"))
      (node (ref "IC2") (pin "B1") (pinfunction "IN/TRIG_B1") (pintype "bidirectional"))
      (node (ref "IC2") (pin "B3") (pinfunction "GND_B3") (pintype "bidirectional"))
      (node (ref "IC3") (pin "8") (pinfunction "GNDIO_8") (pintype "bidirectional"))
      (node (ref "IC3") (pin "9") (pinfunction "GND_9") (pintype "bidirectional"))
      (node (ref "IC9") (pin "B1") (pinfunction "VSEL_B1") (pintype "bidirectional"))
      (node (ref "IC9") (pin "C1") (pinfunction "AGND_C1") (pintype "bidirectional"))
      (node (ref "IC9") (pin "C2") (pinfunction "PGND_1_C2") (pintype "bidirectional"))
      (node (ref "IC9") (pin "C3") (pinfunction "PGND_2_C3") (pintype "bidirectional"))
      (node (ref "J1") (pin "17") (pinfunction "17_17") (pintype "bidirectional"))
      (node (ref "J1") (pin "8") (pinfunction "8_8") (pintype "bidirectional"))
      (node (ref "J1") (pin "MP1") (pinfunction "MP1_MP1") (pintype "bidirectional"))
      (node (ref "J1") (pin "MP2") (pinfunction "MP2_MP2") (pintype "bidirectional"))
      (node (ref "J2") (pin "3") (pinfunction "3_3") (pintype "bidirectional"))
      (node (ref "J2") (pin "5") (pinfunction "5_5") (pintype "bidirectional"))
      (node (ref "J4") (pin "A12_B1") (pinfunction "GND_A12_B1") (pintype "power_in"))
      (node (ref "J4") (pin "A1_B12") (pinfunction "GND_A1_B12") (pintype "power_in"))
      (node (ref "J4") (pin "SH1") (pinfunction "SHIELD_SH1") (pintype "passive"))
      (node (ref "J4") (pin "SH2") (pinfunction "SHIELD_SH2") (pintype "passive"))
      (node (ref "J4") (pin "SH3") (pinfunction "SHIELD_SH3") (pintype "passive"))
      (node (ref "J4") (pin "SH4") (pinfunction "SHIELD_SH4") (pintype "passive"))
      (node (ref "R1_USB") (pin "1") (pinfunction "1_1") (pintype "bidirectional"))
      (node (ref "R2_EP_DR") (pin "1") (pinfunction "1_1") (pintype "bidirectional"))
      (node (ref "R2_USB") (pin "2") (pinfunction "2_2") (pintype "bidirectional"))
      (node (ref "R3") (pin "1") (pinfunction "1_1") (pintype "bidirectional"))
      (node (ref "R9") (pin "1") (pinfunction "1_1") (pintype "bidirectional"))
      (node (ref "R_TYPE_SEL") (pin "1") (pinfunction "1_1") (pintype "bidirectional"))
      (node (ref "SJ1") (pin "1") (pinfunction "1_1") (pintype "passive"))
      (node (ref "SW_DN") (pin "1") (pinfunction "1_1") (pintype "passive"))
      (node (ref "SW_ENT") (pin "1") (pinfunction "1_1") (pintype "passive"))
      (node (ref "SW_UP") (pin "1") (pinfunction "1_1") (pintype "passive"))
      (node (ref "U$1") (pin "P$74") (pinfunction "VSS_PAD_P$74") (pintype "bidirectional"))
      (node (ref "U$1") (pin "P$75") (pinfunction "VSS_PAD_P$75") (pintype "bidirectional"))
      (node (ref "U$1") (pin "P$76") (pinfunction "VSS_PAD_P$76") (pintype "bidirectional"))
      (node (ref "U$1") (pin "P$77") (pinfunction "VSS_PAD_P$77") (pintype "bidirectional"))
      (node (ref "U$1") (pin "P$78") (pinfunction "VSS_PAD_P$78") (pintype "bidirectional"))
      (node (ref "U$1") (pin "P$79") (pinfunction "VSS_PAD_P$79") (pintype "bidirectional"))
      (node (ref "U$1") (pin "P$80") (pinfunction "VSS_PAD_P$80") (pintype "bidirectional"))
      (node (ref "U$1") (pin "P$81") (pinfunction "VSS_PAD_P$81") (pintype "bidirectional"))
      (node (ref "U$1") (pin "P$82") (pinfunction "VSS_PAD_P$82") (pintype "bidirectional"))
      (node (ref "U$1") (pin "P$83") (pinfunction "VSS_PAD_P$83") (pintype "bidirectional"))
      (node (ref "U$1") (pin "P$84") (pinfunction "VSS_PAD_P$84") (pintype "bidirectional"))
      (node (ref "U$1") (pin "P$85") (pinfunction "VSS_PAD_P$85") (pintype "bidirectional"))
      (node (ref "U$1") (pin "P$86") (pinfunction "VSS_PAD_P$86") (pintype "bidirectional"))
      (node (ref "U$1") (pin "P$87") (pinfunction "VSS_PAD_P$87") (pintype "bidirectional"))
      (node (ref "U$1") (pin "P$88") (pinfunction "VSS_PAD_P$88") (pintype "bidirectional"))
      (node (ref "U$1") (pin "P$89") (pinfunction "VSS_PAD_P$89") (pintype "bidirectional"))
      (node (ref "U$1") (pin "P$90") (pinfunction "VSS_PAD_P$90") (pintype "bidirectional"))
      (node (ref "U$1") (pin "P$B7") (pinfunction "VSS_P$B7") (pintype "power_in"))
      (node (ref "U$1") (pin "P$F23") (pinfunction "VSS_PA_P$F23") (pintype "bidirectional"))
      (node (ref "U3") (pin "1") (pinfunction "CTG_1") (pintype "power_in"))
      (node (ref "U3") (pin "4") (pinfunction "GND_4") (pintype "power_in"))
      (node (ref "U3") (pin "6") (pinfunction "QSTRT_6") (pintype "input"))
      (node (ref "U3") (pin "9") (pinfunction "EP_9") (pintype "power_in"))
      (node (ref "X1") (pin "2") (pinfunction "2_2") (pintype "passive"))
      (node (ref "X1") (pin "4") (pinfunction "4_4") (pintype "passive"))
    )
    (net (code "17") (name "HAPTIC_EN") (class "Default")
      (node (ref "IC2") (pin "A1") (pinfunction "EN_A1") (pintype "bidirectional"))
      (node (ref "U$1") (pin "P$U1") (pinfunction "P0.12_P$U1") (pintype "bidirectional"))
    )
    (net (code "18") (name "IMU_INT1") (class "Default")
      (node (ref "IC3") (pin "5") (pinfunction "INT1_5") (pintype "bidirectional"))
      (node (ref "U$1") (pin "P$N1") (pinfunction "P0.08_P$N1") (pintype "bidirectional"))
    )
    (net (code "19") (name "IMU_INT2") (class "Default")
      (node (ref "IC3") (pin "6") (pinfunction "INT2_6") (pintype "bidirectional"))
      (node (ref "U$1") (pin "P$P2") (pinfunction "P1.08_P$P2") (pintype "bidirectional"))
    )
    (net (code "20") (name "LX1") (class "Default")
      (node (ref "IC9") (pin "B2") (pinfunction "SW1_1_B2") (pintype "bidirectional"))
      (node (ref "IC9") (pin "B3") (pinfunction "SW1_2_B3") (pintype "bidirectional"))
      (node (ref "L7") (pin "1") (pinfunction "1_1") (pintype "bidirectional"))
    )
    (net (code "21") (name "LX2") (class "Default")
      (node (ref "IC9") (pin "D2") (pinfunction "SW2_1_D2") (pintype "bidirectional"))
      (node (ref "IC9") (pin "D3") (pinfunction "SW2_2_D3") (pintype "bidirectional"))
      (node (ref "L7") (pin "2") (pinfunction "2_2") (pintype "bidirectional"))
    )
    (net (code "22") (name "MOSI") (class "Default")
      (node (ref "J1") (pin "14") (pinfunction "14_14") (pintype "bidirectional"))
      (node (ref "U$1") (pin "P$B13") (pinfunction "P0.03/AIN1_P$B13") (pintype "bidirectional"))
    )
    (net (code "23") (name "Net-(ANT1-FEED)") (class "Default")
      (node (ref "ANT1") (pin "1") (pinfunction "FEED_1") (pintype "input"))
      (node (ref "C22") (pin "1") (pinfunction "1_1") (pintype "passive"))
      (node (ref "C4") (pin "1") (pinfunction "1_1") (pintype "passive"))
      (node (ref "L1") (pin "2") (pinfunction "2_2") (pintype "passive"))
    )
    (net (code "24") (name "Net-(D2-K)") (class "Default")
      (node (ref "C2-EP-DR") (pin "1") (pinfunction "1_1") (pintype "passive"))
      (node (ref "D2") (pin "1") (pinfunction "K_1") (pintype "bidirectional"))
      (node (ref "D4") (pin "2") (pinfunction "A_2") (pintype "bidirectional"))
    )
    (net (code "25") (name "Net-(D5-A)") (class "Default")
      (node (ref "C2-EP-DR") (pin "2") (pinfunction "2_2") (pintype "passive"))
      (node (ref "D5") (pin "2") (pinfunction "A_2") (pintype "bidirectional"))
      (node (ref "L5") (pin "1") (pinfunction "1_1") (pintype "passive"))
      (node (ref "Q3") (pin "3") (pinfunction "D_3") (pintype "bidirectional"))
    )
    (net (code "26") (name "Net-(EPD_C1-Pad2)") (class "Default")
      (node (ref "EPD_C1") (pin "2") (pinfunction "2_2") (pintype "passive"))
      (node (ref "J1") (pin "5") (pinfunction "5_5") (pintype "bidirectional"))
    )
    (net (code "27") (name "Net-(EPD_C2-Pad2)") (class "Default")
      (node (ref "EPD_C2") (pin "2") (pinfunction "2_2") (pintype "passive"))
      (node (ref "J1") (pin "4") (pinfunction "4_4") (pintype "bidirectional"))
    )
    (net (code "28") (name "Net-(EPD_C6-Pad2)") (class "Default")
      (node (ref "EPD_C6") (pin "2") (pinfunction "2_2") (pintype "passive"))
      (node (ref "J1") (pin "18") (pinfunction "18_18") (pintype "bidirectional"))
    )
    (net (code "29") (name "Net-(EPD_C7-Pad2)") (class "Default")
      (node (ref "EPD_C7") (pin "2") (pinfunction "2_2") (pintype "passive"))
      (node (ref "J1") (pin "19") (pinfunction "19_19") (pintype "bidirectional"))
    )
    (net (code "30") (name "Net-(EPD_C8-Pad2)") (class "Default")
      (node (ref "EPD_C8") (pin "2") (pinfunction "2_2") (pintype "passive"))
      (node (ref "J1") (pin "20") (pinfunction "20_20") (pintype "bidirectional"))
    )
    (net (code "31") (name "Net-(EPD_C10-Pad2)") (class "Default")
      (node (ref "EPD_C10") (pin "2") (pinfunction "2_2") (pintype "passive"))
      (node (ref "J1") (pin "22") (pinfunction "22_22") (pintype "bidirectional"))
    )
    (net (code "32") (name "Net-(EPD_C12-Pad2)") (class "Default")
      (node (ref "EPD_C12") (pin "2") (pinfunction "2_2") (pintype "passive"))
      (node (ref "J1") (pin "24") (pinfunction "24_24") (pintype "bidirectional"))
    )
    (net (code "33") (name "Net-(IC1-TS{slash}MR)") (class "Default")
      (node (ref "IC1") (pin "D1") (pinfunction "TS/MR_D1") (pintype "bidirectional"))
      (node (ref "R9") (pin "2") (pinfunction "2_2") (pintype "bidirectional"))
    )
    (net (code "34") (name "Net-(IC2-REG)") (class "Default")
      (node (ref "C32") (pin "1") (pinfunction "1_1") (pintype "passive"))
      (node (ref "IC2") (pin "A2") (pinfunction "REG_A2") (pintype "bidirectional"))
    )
    (net (code "35") (name "Net-(IC3-SDO)") (class "Default")
      (node (ref "IC3") (pin "1") (pinfunction "SDO_1") (pintype "bidirectional"))
      (node (ref "R3") (pin "2") (pinfunction "2_2") (pintype "bidirectional"))
    )
    (net (code "36") (name "Net-(IC9-SCL)") (class "Default")
      (node (ref "IC9") (pin "D1") (pinfunction "SCL_D1") (pintype "bidirectional"))
      (node (ref "R4") (pin "2") (pinfunction "2_2") (pintype "bidirectional"))
    )
    (net (code "37") (name "Net-(IC9-SDA)") (class "Default")
      (node (ref "IC9") (pin "E1") (pinfunction "SDA_E1") (pintype "bidirectional"))
      (node (ref "R1") (pin "2") (pinfunction "2_2") (pintype "bidirectional"))
    )
    (net (code "38") (name "Net-(J4-CC1)") (class "Default")
      (node (ref "J4") (pin "A5") (pinfunction "CC1_A5") (pintype "bidirectional"))
      (node (ref "R1_USB") (pin "2") (pinfunction "2_2") (pintype "bidirectional"))
    )
    (net (code "39") (name "Net-(J4-CC2)") (class "Default")
      (node (ref "J4") (pin "B5") (pinfunction "CC2_B5") (pintype "bidirectional"))
      (node (ref "R2_USB") (pin "1") (pinfunction "1_1") (pintype "bidirectional"))
    )
    (net (code "40") (name "Net-(L2-Pad2)") (class "Default")
      (node (ref "L2") (pin "2") (pinfunction "2_2") (pintype "passive"))
      (node (ref "L3") (pin "1") (pinfunction "1_1") (pintype "passive"))
    )
    (net (code "41") (name "Net-(R1_EP_DR-Pad1)") (class "Default")
      (node (ref "R1_EP_DR") (pin "1") (pinfunction "1_1") (pintype "bidirectional"))
      (node (ref "R_TYPE_SEL") (pin "2") (pinfunction "2_2") (pintype "bidirectional"))
      (node (ref "SJ1") (pin "2") (pinfunction "2_2") (pintype "passive"))
    )
    (net (code "42") (name "Net-(U$1-ANT)") (class "Default")
      (node (ref "C3") (pin "1") (pinfunction "1_1") (pintype "passive"))
      (node (ref "L1") (pin "1") (pinfunction "1_1") (pintype "passive"))
      (node (ref "U$1") (pin "P$H23") (pinfunction "ANT_P$H23") (pintype "bidirectional"))
    )
    (net (code "43") (name "Net-(U$1-DCC)") (class "Default")
      (node (ref "L2") (pin "1") (pinfunction "1_1") (pintype "passive"))
      (node (ref "U$1") (pin "P$B3") (pinfunction "DCC_P$B3") (pintype "output"))
    )
    (net (code "44") (name "Net-(U$1-DEC1)") (class "Default")
      (node (ref "C5") (pin "1") (pinfunction "1_1") (pintype "passive"))
      (node (ref "U$1") (pin "P$C1") (pinfunction "DEC1_P$C1") (pintype "power_in"))
    )
    (net (code "45") (name "Net-(U$1-DEC2)") (class "Default")
      (node (ref "C13") (pin "1") (pinfunction "1_1") (pintype "passive"))
      (node (ref "U$1") (pin "P$A18") (pinfunction "DEC2_P$A18") (pintype "bidirectional"))
    )
    (net (code "46") (name "Net-(U$1-DEC3V3)") (class "Default")
      (node (ref "C20") (pin "1") (pinfunction "1_1") (pintype "passive"))
      (node (ref "U$1") (pin "P$AC5") (pinfunction "DEC3V3_P$AC5") (pintype "bidirectional"))
    )
    (net (code "47") (name "Net-(U$1-DEC5)") (class "Default")
      (node (ref "C9") (pin "1") (pinfunction "1_1") (pintype "passive"))
      (node (ref "U$1") (pin "P$N24") (pinfunction "DEC5_P$N24") (pintype "bidirectional"))
    )
    (net (code "48") (name "Net-(U$1-P0.00{slash}XL1)") (class "Default")
      (node (ref "C17") (pin "2") (pinfunction "2_2") (pintype "passive"))
      (node (ref "U$1") (pin "P$D2") (pinfunction "P0.00/XL1_P$D2") (pintype "bidirectional"))
      (node (ref "X2") (pin "1") (pinfunction "1_1") (pintype "passive"))
    )
    (net (code "49") (name "Net-(U$1-P0.01{slash}XL2)") (class "Default")
      (node (ref "C18") (pin "2") (pinfunction "2_2") (pintype "passive"))
      (node (ref "U$1") (pin "P$F2") (pinfunction "P0.01/XL2_P$F2") (pintype "bidirectional"))
      (node (ref "X2") (pin "2") (pinfunction "2_2") (pintype "passive"))
    )
    (net (code "50") (name "Net-(U$1-XC1)") (class "Default")
      (node (ref "C1") (pin "1") (pinfunction "1_1") (pintype "passive"))
      (node (ref "U$1") (pin "P$B24") (pinfunction "XC1_P$B24") (pintype "input"))
      (node (ref "X1") (pin "1") (pinfunction "1_1") (pintype "passive"))
    )
    (net (code "51") (name "Net-(U$1-XC2)") (class "Default")
      (node (ref "C2") (pin "1") (pinfunction "1_1") (pintype "passive"))
      (node (ref "U$1") (pin "P$A23") (pinfunction "XC2_P$A23") (pintype "output"))
      (node (ref "X1") (pin "3") (pinfunction "3_3") (pintype "passive"))
    )
    (net (code "52") (name "OUT+") (class "Default")
      (node (ref "IC2") (pin "A3") (pinfunction "OUT+_A3") (pintype "bidirectional"))
      (node (ref "OP") (pin "TP") (pinfunction "TP_TP") (pintype "input"))
    )
    (net (code "53") (name "OUT-") (class "Default")
      (node (ref "IC2") (pin "C3") (pinfunction "OUT-_C3") (pintype "bidirectional"))
      (node (ref "ON") (pin "TP") (pinfunction "TP_TP") (pintype "input"))
    )
    (net (code "54") (name "P0.04") (class "Default")
      (node (ref "U$1") (pin "P$J1") (pinfunction "P0.04/AIN2_P$J1") (pintype "bidirectional"))
    )
    (net (code "55") (name "P0.09") (class "Default")
      (node (ref "U$1") (pin "P$L24") (pinfunction "P0.09/NFC1_P$L24") (pintype "bidirectional"))
    )
    (net (code "56") (name "P0.13") (class "Default")
      (node (ref "C30") (pin "1") (pinfunction "1_1") (pintype "passive"))
      (node (ref "R5") (pin "1") (pinfunction "1_1") (pintype "bidirectional"))
      (node (ref "SW_UP") (pin "2") (pinfunction "2_2") (pintype "passive"))
      (node (ref "U$1") (pin "P$AD8") (pinfunction "P0.13_P$AD8") (pintype "bidirectional"))
    )
    (net (code "57") (name "P0.14") (class "Default")
      (node (ref "C31") (pin "1") (pinfunction "1_1") (pintype "passive"))
      (node (ref "R8") (pin "1") (pinfunction "1_1") (pintype "bidirectional"))
      (node (ref "SW_ENT") (pin "2") (pinfunction "2_2") (pintype "passive"))
      (node (ref "U$1") (pin "P$AC9") (pinfunction "P0.14_P$AC9") (pintype "bidirectional"))
    )
    (net (code "58") (name "P0.19") (class "Default")
      (node (ref "U$1") (pin "P$AC15") (pinfunction "P0.19_P$AC15") (pintype "bidirectional"))
    )
    (net (code "59") (name "P0.20") (class "Default")
      (node (ref "U$1") (pin "P$AD16") (pinfunction "P0.20_P$AD16") (pintype "bidirectional"))
    )
    (net (code "60") (name "P0.21") (class "Default")
      (node (ref "U$1") (pin "P$AC17") (pinfunction "P0.21_P$AC17") (pintype "bidirectional"))
    )
    (net (code "61") (name "P0.22") (class "Default")
      (node (ref "U$1") (pin "P$AD18") (pinfunction "P0.22_P$AD18") (pintype "bidirectional"))
    )
    (net (code "62") (name "P0.23") (class "Default")
      (node (ref "U$1") (pin "P$AC19") (pinfunction "P0.23_P$AC19") (pintype "bidirectional"))
    )
    (net (code "63") (name "P0.24") (class "Default")
      (node (ref "U$1") (pin "P$AD20") (pinfunction "P0.24_P$AD20") (pintype "bidirectional"))
    )
    (net (code "64") (name "P0.25") (class "Default")
      (node (ref "U$1") (pin "P$AC21") (pinfunction "P0.25_P$AC21") (pintype "bidirectional"))
    )
    (net (code "65") (name "P0.26") (class "Default")
      (node (ref "U$1") (pin "P$G1") (pinfunction "P0.26_P$G1") (pintype "bidirectional"))
    )
    (net (code "66") (name "P0.27") (class "Default")
      (node (ref "U$1") (pin "P$H2") (pinfunction "P0.27_P$H2") (pintype "bidirectional"))
    )
    (net (code "67") (name "P0.28") (class "Default")
      (node (ref "U$1") (pin "P$B11") (pinfunction "P0.28/AIN4_P$B11") (pintype "bidirectional"))
    )
    (net (code "68") (name "P0.29") (class "Default")
      (node (ref "U$1") (pin "P$A10") (pinfunction "P0.29/AIN5_P$A10") (pintype "bidirectional"))
    )
    (net (code "69") (name "P0.30") (class "Default")
      (node (ref "U$1") (pin "P$B9") (pinfunction "P0.30/AIN6_P$B9") (pintype "bidirectional"))
    )
    (net (code "70") (name "P0.31") (class "Default")
      (node (ref "U$1") (pin "P$A8") (pinfunction "P0.31/AIN7_P$A8") (pintype "bidirectional"))
    )
    (net (code "71") (name "P1.01") (class "Default")
      (node (ref "Q1") (pin "1") (pinfunction "G_1") (pintype "bidirectional"))
      (node (ref "R_PWR_EPD") (pin "1") (pinfunction "1_1") (pintype "bidirectional"))
      (node (ref "U$1") (pin "P$Y23") (pinfunction "P1.01_P$Y23") (pintype "bidirectional"))
    )
    (net (code "72") (name "P1.02") (class "Default")
      (node (ref "C29") (pin "1") (pinfunction "1_1") (pintype "passive"))
      (node (ref "R7") (pin "1") (pinfunction "1_1") (pintype "bidirectional"))
      (node (ref "SW_DN") (pin "2") (pinfunction "2_2") (pintype "passive"))
      (node (ref "U$1") (pin "P$W24") (pinfunction "P1.02_P$W24") (pintype "bidirectional"))
    )
    (net (code "73") (name "P1.03") (class "Default")
      (node (ref "U$1") (pin "P$V23") (pinfunction "P1.03_P$V23") (pintype "bidirectional"))
    )
    (net (code "74") (name "P1.04") (class "Default")
      (node (ref "U$1") (pin "P$U24") (pinfunction "P1.04_P$U24") (pintype "bidirectional"))
    )
    (net (code "75") (name "P1.05") (class "Default")
      (node (ref "U$1") (pin "P$T23") (pinfunction "P1.05_P$T23") (pintype "bidirectional"))
    )
    (net (code "76") (name "P1.06") (class "Default")
      (node (ref "U$1") (pin "P$R24") (pinfunction "P1.06_P$R24") (pintype "bidirectional"))
    )
    (net (code "77") (name "P1.07") (class "Default")
      (node (ref "U$1") (pin "P$P23") (pinfunction "P1.07_P$P23") (pintype "bidirectional"))
    )
    (net (code "78") (name "P1.09") (class "Default")
      (node (ref "U$1") (pin "P$R1") (pinfunction "P1.09_P$R1") (pintype "bidirectional"))
    )
    (net (code "79") (name "P1.10") (class "Default")
      (node (ref "U$1") (pin "P$A20") (pinfunction "P1.10_P$A20") (pintype "bidirectional"))
    )
    (net (code "80") (name "P1.11") (class "Default")
      (node (ref "U$1") (pin "P$B19") (pinfunction "P1.11_P$B19") (pintype "bidirectional"))
    )
    (net (code "81") (name "P1.12") (class "Default")
      (node (ref "U$1") (pin "P$B17") (pinfunction "P1.12_P$B17") (pintype "bidirectional"))
    )
    (net (code "82") (name "P1.13") (class "Default")
      (node (ref "U$1") (pin "P$A16") (pinfunction "P1.13_P$A16") (pintype "bidirectional"))
    )
    (net (code "83") (name "P1.14") (class "Default")
      (node (ref "U$1") (pin "P$B15") (pinfunction "P1.14_P$B15") (pintype "bidirectional"))
    )
    (net (code "84") (name "P1.15") (class "Default")
      (node (ref "U$1") (pin "P$A14") (pinfunction "P1.15_P$A14") (pintype "bidirectional"))
    )
    (net (code "85") (name "PMIC_INT") (class "Default")
      (node (ref "IC1") (pin "A1") (pinfunction "~{INT}_A1") (pintype "bidirectional"))
      (node (ref "U$1") (pin "P$T2") (pinfunction "P0.11_P$T2") (pintype "bidirectional"))
    )
    (net (code "86") (name "PREVGH") (class "Default")
      (node (ref "D5") (pin "1") (pinfunction "K_1") (pintype "bidirectional"))
      (node (ref "EPD_C9") (pin "2") (pinfunction "2_2") (pintype "passive"))
      (node (ref "J1") (pin "21") (pinfunction "21_21") (pintype "bidirectional"))
    )
    (net (code "87") (name "PREVGL") (class "Default")
      (node (ref "D2") (pin "2") (pinfunction "A_2") (pintype "bidirectional"))
      (node (ref "EPD_C11") (pin "2") (pinfunction "2_2") (pintype "passive"))
      (node (ref "J1") (pin "23") (pinfunction "23_23") (pintype "bidirectional"))
    )
    (net (code "88") (name "RESE") (class "Default")
      (node (ref "J1") (pin "3") (pinfunction "3_3") (pintype "bidirectional"))
      (node (ref "Q3") (pin "2") (pinfunction "S_2") (pintype "bidirectional"))
      (node (ref "R1_EP_DR") (pin "2") (pinfunction "2_2") (pintype "bidirectional"))
    )
    (net (code "89") (name "RESET") (class "Default")
      (node (ref "J2") (pin "6") (pinfunction "6_6") (pintype "bidirectional"))
      (node (ref "RESET") (pin "TP") (pinfunction "TP_TP") (pintype "input"))
      (node (ref "U$1") (pin "P$AC13") (pinfunction "P0.18/RESET_P$AC13") (pintype "bidirectional"))
    )
    (net (code "90") (name "SCK") (class "Default")
      (node (ref "J1") (pin "13") (pinfunction "13_13") (pintype "bidirectional"))
      (node (ref "U$1") (pin "P$A12") (pinfunction "P0.02/AIN0_P$A12") (pintype "bidirectional"))
    )
    (net (code "91") (name "SCL") (class "Default")
      (node (ref "IC1") (pin "B1") (pinfunction "SCL_B1") (pintype "bidirectional"))
      (node (ref "IC2") (pin "C1") (pinfunction "SCL_C1") (pintype "bidirectional"))
      (node (ref "IC3") (pin "12") (pinfunction "SCX_12") (pintype "bidirectional"))
      (node (ref "R17") (pin "2") (pinfunction "2_2") (pintype "bidirectional"))
      (node (ref "R4") (pin "1") (pinfunction "1_1") (pintype "bidirectional"))
      (node (ref "SCL") (pin "TP") (pinfunction "TP_TP") (pintype "input"))
      (node (ref "U$1") (pin "P$M2") (pinfunction "P0.07_P$M2") (pintype "bidirectional"))
      (node (ref "U3") (pin "7") (pinfunction "SCL_7") (pintype "input"))
    )
    (net (code "92") (name "SDA") (class "Default")
      (node (ref "IC1") (pin "C1") (pinfunction "SDA_C1") (pintype "bidirectional"))
      (node (ref "IC2") (pin "B2") (pinfunction "SDA_B2") (pintype "bidirectional"))
      (node (ref "IC3") (pin "2") (pinfunction "SDX_2") (pintype "bidirectional"))
      (node (ref "R1") (pin "1") (pinfunction "1_1") (pintype "bidirectional"))
      (node (ref "R18") (pin "2") (pinfunction "2_2") (pintype "bidirectional"))
      (node (ref "SDA") (pin "TP") (pinfunction "TP_TP") (pintype "input"))
      (node (ref "U$1") (pin "P$L1") (pinfunction "P0.06_P$L1") (pintype "bidirectional"))
      (node (ref "U3") (pin "8") (pinfunction "SDA_8") (pintype "bidirectional"))
    )
    (net (code "93") (name "SWDCLK") (class "Default")
      (node (ref "J2") (pin "4") (pinfunction "4_4") (pintype "bidirectional"))
      (node (ref "SWDCLK") (pin "TP") (pinfunction "TP_TP") (pintype "input"))
      (node (ref "U$1") (pin "P$AA24") (pinfunction "SWDCLK_P$AA24") (pintype "input"))
    )
    (net (code "94") (name "SWDIO") (class "Default")
      (node (ref "J2") (pin "2") (pinfunction "2_2") (pintype "bidirectional"))
      (node (ref "SWDIO") (pin "TP") (pinfunction "TP_TP") (pintype "input"))
      (node (ref "U$1") (pin "P$AC24") (pinfunction "SWDIO_P$AC24") (pintype "bidirectional"))
    )
    (net (code "95") (name "SWO") (class "Default")
      (node (ref "SWO") (pin "TP") (pinfunction "TP_TP") (pintype "input"))
      (node (ref "U$1") (pin "P$AD22") (pinfunction "P1.00_P$AD22") (pintype "bidirectional"))
    )
    (net (code "96") (name "VBAT") (class "Default")
      (node (ref "C27") (pin "1") (pinfunction "1_1") (pintype "passive"))
      (node (ref "C37") (pin "1") (pinfunction "1_1") (pintype "passive"))
      (node (ref "IC1") (pin "C2") (pinfunction "BAT_C2") (pintype "bidirectional"))
      (node (ref "U3") (pin "2") (pinfunction "CELL_2") (pintype "power_in"))
      (node (ref "U3") (pin "3") (pinfunction "VDD_3") (pintype "power_in"))
      (node (ref "VBAT") (pin "TP") (pinfunction "TP_TP") (pintype "input"))
    )
    (net (code "97") (name "VBUS") (class "Default")
      (node (ref "C21") (pin "1") (pinfunction "1_1") (pintype "passive"))
      (node (ref "C38") (pin "1") (pinfunction "1_1") (pintype "passive"))
      (node (ref "C42") (pin "1") (pinfunction "1_1") (pintype "passive"))
      (node (ref "C43") (pin "1") (pinfunction "1_1") (pintype "passive"))
      (node (ref "D3") (pin "5") (pinfunction "VBUS_5") (pintype "bidirectional"))
      (node (ref "IC1") (pin "A2") (pinfunction "IN_A2") (pintype "bidirectional"))
      (node (ref "J4") (pin "A4_B9") (pinfunction "VBUS_A4_B9") (pintype "power_in"))
      (node (ref "J4") (pin "A9_B4") (pinfunction "VBUS_A9_B4") (pintype "power_in"))
      (node (ref "U$1") (pin "P$AD2") (pinfunction "VBUS_P$AD2") (pintype "power_in"))
    )
    (net (code "98") (name "VREG") (class "Default")
      (node (ref "C23") (pin "2") (pinfunction "2_2") (pintype "passive"))
      (node (ref "C24") (pin "2") (pinfunction "2_2") (pintype "passive"))
      (node (ref "C39") (pin "1") (pinfunction "1_1") (pintype "passive"))
      (node (ref "IC1") (pin "B2") (pinfunction "SYS_B2") (pintype "bidirectional"))
      (node (ref "IC9") (pin "A1") (pinfunction "EN_A1") (pintype "bidirectional"))
      (node (ref "IC9") (pin "A2") (pinfunction "VIN_1_A2") (pintype "bidirectional"))
      (node (ref "IC9") (pin "A3") (pinfunction "VIN_2_A3") (pintype "bidirectional"))
      (node (ref "VREG") (pin "TP") (pinfunction "TP_TP") (pintype "input"))
    )
    (net (code "99") (name "unconnected-(ANT1-NC-Pad2)") (class "Default")
      (node (ref "ANT1") (pin "2") (pinfunction "NC_2") (pintype "no_connect"))
    )
    (net (code "100") (name "unconnected-(IC3-ASCL-Pad11)") (class "Default")
      (node (ref "IC3") (pin "11") (pinfunction "ASCL_11") (pintype "bidirectional"))
    )
    (net (code "101") (name "unconnected-(IC3-ASDA-Pad4)") (class "Default")
      (node (ref "IC3") (pin "4") (pinfunction "ASDA_4") (pintype "bidirectional"))
    )
    (net (code "102") (name "unconnected-(J1-Pad1)") (class "Default")
      (node (ref "J1") (pin "1") (pinfunction "1_1") (pintype "bidirectional"))
    )
    (net (code "103") (name "unconnected-(J1-Pad6)") (class "Default")
      (node (ref "J1") (pin "6") (pinfunction "6_6") (pintype "bidirectional"))
    )
    (net (code "104") (name "unconnected-(J1-Pad7)") (class "Default")
      (node (ref "J1") (pin "7") (pinfunction "7_7") (pintype "bidirectional"))
    )
    (net (code "105") (name "unconnected-(J4-SBU1-PadA8)") (class "Default")
      (node (ref "J4") (pin "A8") (pinfunction "SBU1_A8") (pintype "bidirectional"))
    )
    (net (code "106") (name "unconnected-(J4-SBU2-PadB8)") (class "Default")
      (node (ref "J4") (pin "B8") (pinfunction "SBU2_B8") (pintype "bidirectional"))
    )
    (net (code "107") (name "unconnected-(U$1-DCCH-PadP$AB2)") (class "Default")
      (node (ref "U$1") (pin "P$AB2") (pinfunction "DCCH_P$AB2") (pintype "bidirectional"))
    )
  )
)
